# devboard.net
KiCad netlist of a schematic drawn in EAGLE
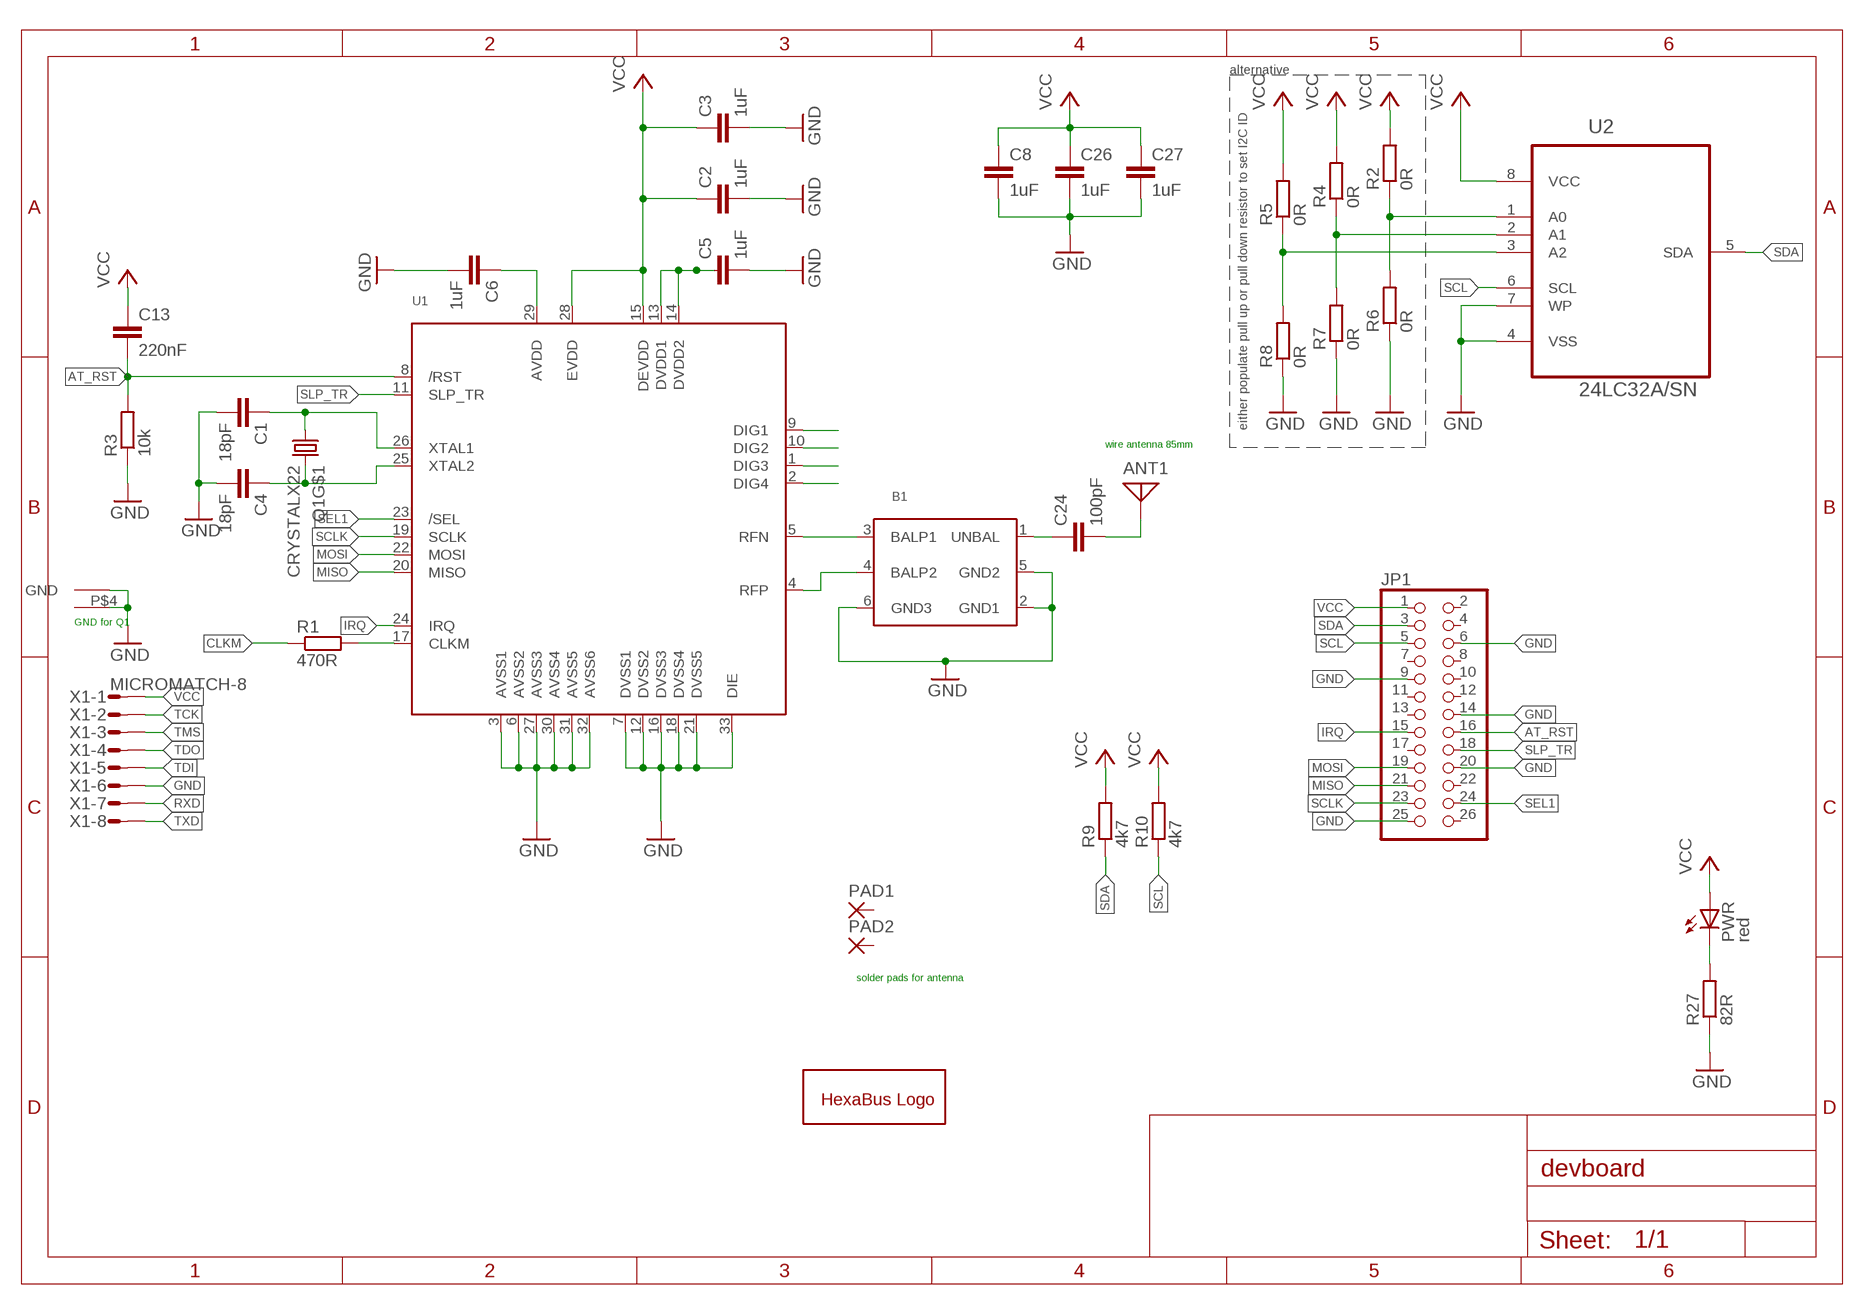
[diagram p0: schematic, sheet 1]

(export (version "E")
  (design (tool "Eeschema 10.0.6"))
  (components
    (comp (ref "ANT1")
      (value "ANTENNA")
      (footprint "eagle-import:PAD-01")
      (libsource (lib "eagle-import") (part "ANTENNA"))
    )
    (comp (ref "B1")
      (value "BALUN+LP")
      (footprint "eagle-import:BALUN0805")
      (libsource (lib "eagle-import") (part "BALUN+LP"))
    )
    (comp (ref "C1")
      (value "18pF")
      (footprint "eagle-import:C0603")
      (libsource (lib "eagle-import") (part "C-EUC0603"))
    )
    (comp (ref "C2")
      (value "1uF")
      (footprint "eagle-import:C0603")
      (libsource (lib "eagle-import") (part "C-EUC0603"))
    )
    (comp (ref "C3")
      (value "1uF")
      (footprint "eagle-import:C0603")
      (libsource (lib "eagle-import") (part "C-EUC0603"))
    )
    (comp (ref "C4")
      (value "18pF")
      (footprint "eagle-import:C0603")
      (libsource (lib "eagle-import") (part "C-EUC0603"))
    )
    (comp (ref "C5")
      (value "1uF")
      (footprint "eagle-import:C0603")
      (libsource (lib "eagle-import") (part "C-EUC0603"))
    )
    (comp (ref "C6")
      (value "1uF")
      (footprint "eagle-import:C0603")
      (libsource (lib "eagle-import") (part "C-EUC0603"))
    )
    (comp (ref "C8")
      (value "1uF")
      (footprint "eagle-import:C0603")
      (libsource (lib "eagle-import") (part "C-EUC0603"))
    )
    (comp (ref "C13")
      (value "220nF")
      (footprint "eagle-import:C0603")
      (libsource (lib "eagle-import") (part "C-EUC0603"))
    )
    (comp (ref "C24")
      (value "100pF")
      (footprint "eagle-import:C0603")
      (libsource (lib "eagle-import") (part "C-EUC0603"))
    )
    (comp (ref "C26")
      (value "1uF")
      (footprint "eagle-import:C0603")
      (libsource (lib "eagle-import") (part "C-EUC0603"))
    )
    (comp (ref "C27")
      (value "1uF")
      (footprint "eagle-import:C0603")
      (libsource (lib "eagle-import") (part "C-EUC0603"))
    )
    (comp (ref "JP1")
      (value "PINHD-2X13")
      (footprint "eagle-import:2X13")
      (libsource (lib "eagle-import") (part "PINHD-2X13"))
    )
    (comp (ref "PAD1")
      (value "SMD2")
      (footprint "eagle-import:SMD1,27-2,54")
      (libsource (lib "eagle-import") (part "SMD2"))
    )
    (comp (ref "PAD2")
      (value "SMD2")
      (footprint "eagle-import:SMD1,27-2,54")
      (libsource (lib "eagle-import") (part "SMD2"))
    )
    (comp (ref "PWR")
      (value "red")
      (footprint "eagle-import:CHIP-LED0603")
      (libsource (lib "eagle-import") (part "LEDCHIP-LED0603"))
    )
    (comp (ref "Q1")
      (value "CRYSTALX22")
      (footprint "eagle-import:X22")
      (libsource (lib "eagle-import") (part "CRYSTALX22"))
    )
    (comp (ref "R1")
      (value "470R")
      (footprint "eagle-import:R0603")
      (libsource (lib "eagle-import") (part "R-EU_R0603"))
    )
    (comp (ref "R2")
      (value "0R")
      (footprint "eagle-import:R0603")
      (libsource (lib "eagle-import") (part "R-EU_R0603"))
    )
    (comp (ref "R3")
      (value "10k")
      (footprint "eagle-import:R0603")
      (libsource (lib "eagle-import") (part "R-EU_R0603"))
    )
    (comp (ref "R4")
      (value "0R")
      (footprint "eagle-import:R0603")
      (libsource (lib "eagle-import") (part "R-EU_R0603"))
    )
    (comp (ref "R5")
      (value "0R")
      (footprint "eagle-import:R0603")
      (libsource (lib "eagle-import") (part "R-EU_R0603"))
    )
    (comp (ref "R6")
      (value "0R")
      (footprint "eagle-import:R0603")
      (libsource (lib "eagle-import") (part "R-EU_R0603"))
    )
    (comp (ref "R7")
      (value "0R")
      (footprint "eagle-import:R0603")
      (libsource (lib "eagle-import") (part "R-EU_R0603"))
    )
    (comp (ref "R8")
      (value "0R")
      (footprint "eagle-import:R0603")
      (libsource (lib "eagle-import") (part "R-EU_R0603"))
    )
    (comp (ref "R9")
      (value "4k7")
      (footprint "eagle-import:R0603")
      (libsource (lib "eagle-import") (part "R-EU_R0603"))
    )
    (comp (ref "R10")
      (value "4k7")
      (footprint "eagle-import:R0603")
      (libsource (lib "eagle-import") (part "R-EU_R0603"))
    )
    (comp (ref "R27")
      (value "82R")
      (footprint "eagle-import:R0603")
      (libsource (lib "eagle-import") (part "R-EU_R0603"))
    )
    (comp (ref "U$1")
      (value "HEXAKRAKE")
      (footprint "eagle-import:HEXAKRAKE")
      (libsource (lib "eagle-import") (part "HEXAKRAKE"))
    )
    (comp (ref "U1")
      (value "AT86RF212")
      (footprint "eagle-import:32QN2")
      (libsource (lib "eagle-import") (part "AT86RF212"))
    )
    (comp (ref "U2")
      (value "24LC32A/SN")
      (footprint "eagle-import:SOIC127P600X175-8N")
      (libsource (lib "eagle-import") (part "24LC32A/SN"))
    )
    (comp (ref "X1")
      (value "MICROMATCH-8")
      (footprint "eagle-import:MICROMATCH-8")
      (fields (field (name "MF") "FARNELL") (field (name "MPN") "7-215464-8"))
      (libsource (lib "eagle-import") (part "MICROMATCH-8"))
    )
  )
  (nets
    (net (code "1") (name "AT_RST") (class "Default")
      (node (ref "C13") (pin "2") (pinfunction "2_2") (pintype "passive"))
      (node (ref "JP1") (pin "16") (pinfunction "16_16") (pintype "passive"))
      (node (ref "R3") (pin "2") (pinfunction "2_2") (pintype "passive"))
      (node (ref "U1") (pin "8") (pinfunction "/RST_8") (pintype "bidirectional"))
    )
    (net (code "2") (name "CLKM") (class "Default")
      (node (ref "R1") (pin "1") (pinfunction "1_1") (pintype "passive"))
    )
    (net (code "3") (name "GND") (class "Default")
      (node (ref "B1") (pin "2") (pinfunction "GND1_2") (pintype "bidirectional"))
      (node (ref "B1") (pin "5") (pinfunction "GND2_5") (pintype "bidirectional"))
      (node (ref "B1") (pin "6") (pinfunction "GND3_6") (pintype "bidirectional"))
      (node (ref "C1") (pin "2") (pinfunction "2_2") (pintype "passive"))
      (node (ref "C2") (pin "2") (pinfunction "2_2") (pintype "passive"))
      (node (ref "C26") (pin "2") (pinfunction "2_2") (pintype "passive"))
      (node (ref "C27") (pin "2") (pinfunction "2_2") (pintype "passive"))
      (node (ref "C3") (pin "2") (pinfunction "2_2") (pintype "passive"))
      (node (ref "C4") (pin "2") (pinfunction "2_2") (pintype "passive"))
      (node (ref "C5") (pin "2") (pinfunction "2_2") (pintype "passive"))
      (node (ref "C6") (pin "2") (pinfunction "2_2") (pintype "passive"))
      (node (ref "C8") (pin "2") (pinfunction "2_2") (pintype "passive"))
      (node (ref "JP1") (pin "14") (pinfunction "14_14") (pintype "passive"))
      (node (ref "JP1") (pin "20") (pinfunction "20_20") (pintype "passive"))
      (node (ref "JP1") (pin "25") (pinfunction "25_25") (pintype "passive"))
      (node (ref "JP1") (pin "6") (pinfunction "6_6") (pintype "passive"))
      (node (ref "JP1") (pin "9") (pinfunction "9_9") (pintype "passive"))
      (node (ref "Q1") (pin "P$2") (pinfunction "GND_P$2") (pintype "bidirectional"))
      (node (ref "Q1") (pin "P$4") (pinfunction "GND1_P$4") (pintype "bidirectional"))
      (node (ref "R27") (pin "1") (pinfunction "1_1") (pintype "passive"))
      (node (ref "R3") (pin "1") (pinfunction "1_1") (pintype "passive"))
      (node (ref "R6") (pin "1") (pinfunction "1_1") (pintype "passive"))
      (node (ref "R7") (pin "1") (pinfunction "1_1") (pintype "passive"))
      (node (ref "R8") (pin "1") (pinfunction "1_1") (pintype "passive"))
      (node (ref "U1") (pin "12") (pinfunction "DVSS2_12") (pintype "bidirectional"))
      (node (ref "U1") (pin "16") (pinfunction "DVSS3_16") (pintype "bidirectional"))
      (node (ref "U1") (pin "18") (pinfunction "DVSS4_18") (pintype "bidirectional"))
      (node (ref "U1") (pin "21") (pinfunction "DVSS5_21") (pintype "bidirectional"))
      (node (ref "U1") (pin "27") (pinfunction "AVSS3_27") (pintype "bidirectional"))
      (node (ref "U1") (pin "3") (pinfunction "AVSS1_3") (pintype "bidirectional"))
      (node (ref "U1") (pin "30") (pinfunction "AVSS4_30") (pintype "bidirectional"))
      (node (ref "U1") (pin "31") (pinfunction "AVSS5_31") (pintype "bidirectional"))
      (node (ref "U1") (pin "32") (pinfunction "AVSS6_32") (pintype "bidirectional"))
      (node (ref "U1") (pin "33") (pinfunction "DIE_33") (pintype "bidirectional"))
      (node (ref "U1") (pin "6") (pinfunction "AVSS2_6") (pintype "bidirectional"))
      (node (ref "U1") (pin "7") (pinfunction "DVSS1_7") (pintype "bidirectional"))
      (node (ref "U2") (pin "4") (pinfunction "VSS_4") (pintype "passive"))
      (node (ref "U2") (pin "7") (pinfunction "WP_7") (pintype "input"))
      (node (ref "X1") (pin "6") (pinfunction "S_6") (pintype "passive"))
    )
    (net (code "4") (name "IRQ") (class "Default")
      (node (ref "JP1") (pin "15") (pinfunction "15_15") (pintype "passive"))
      (node (ref "U1") (pin "24") (pinfunction "IRQ_24") (pintype "bidirectional"))
    )
    (net (code "5") (name "MISO") (class "Default")
      (node (ref "JP1") (pin "21") (pinfunction "21_21") (pintype "passive"))
      (node (ref "U1") (pin "20") (pinfunction "MISO_20") (pintype "bidirectional"))
    )
    (net (code "6") (name "MOSI") (class "Default")
      (node (ref "JP1") (pin "19") (pinfunction "19_19") (pintype "passive"))
      (node (ref "U1") (pin "22") (pinfunction "MOSI_22") (pintype "bidirectional"))
    )
    (net (code "7") (name "Net-(ANT1-Pad1)") (class "Default")
      (node (ref "ANT1") (pin "1") (pinfunction "1_1") (pintype "output"))
      (node (ref "C24") (pin "2") (pinfunction "2_2") (pintype "passive"))
    )
    (net (code "8") (name "Net-(B1-BALP1)") (class "Default")
      (node (ref "B1") (pin "3") (pinfunction "BALP1_3") (pintype "bidirectional"))
      (node (ref "U1") (pin "5") (pinfunction "RFN_5") (pintype "bidirectional"))
    )
    (net (code "9") (name "Net-(B1-BALP2)") (class "Default")
      (node (ref "B1") (pin "4") (pinfunction "BALP2_4") (pintype "bidirectional"))
      (node (ref "U1") (pin "4") (pinfunction "RFP_4") (pintype "bidirectional"))
    )
    (net (code "10") (name "Net-(B1-UNBAL)") (class "Default")
      (node (ref "B1") (pin "1") (pinfunction "UNBAL_1") (pintype "bidirectional"))
      (node (ref "C24") (pin "1") (pinfunction "1_1") (pintype "passive"))
    )
    (net (code "11") (name "Net-(PWR-PadC)") (class "Default")
      (node (ref "PWR") (pin "C") (pinfunction "C_C") (pintype "passive"))
      (node (ref "R27") (pin "2") (pinfunction "2_2") (pintype "passive"))
    )
    (net (code "12") (name "Net-(Q1A-1)") (class "Default")
      (node (ref "C1") (pin "1") (pinfunction "1_1") (pintype "passive"))
      (node (ref "Q1") (pin "P$1") (pinfunction "1_P$1") (pintype "passive"))
      (node (ref "U1") (pin "26") (pinfunction "XTAL1_26") (pintype "bidirectional"))
    )
    (net (code "13") (name "Net-(Q1A-2)") (class "Default")
      (node (ref "C4") (pin "1") (pinfunction "1_1") (pintype "passive"))
      (node (ref "Q1") (pin "P$3") (pinfunction "2_P$3") (pintype "passive"))
      (node (ref "U1") (pin "25") (pinfunction "XTAL2_25") (pintype "bidirectional"))
    )
    (net (code "14") (name "Net-(U1-AVDD)") (class "Default")
      (node (ref "C6") (pin "1") (pinfunction "1_1") (pintype "passive"))
      (node (ref "U1") (pin "29") (pinfunction "AVDD_29") (pintype "bidirectional"))
    )
    (net (code "15") (name "Net-(U1-CLKM)") (class "Default")
      (node (ref "R1") (pin "2") (pinfunction "2_2") (pintype "passive"))
      (node (ref "U1") (pin "17") (pinfunction "CLKM_17") (pintype "bidirectional"))
    )
    (net (code "16") (name "Net-(U1-DVDD1)") (class "Default")
      (node (ref "C5") (pin "1") (pinfunction "1_1") (pintype "passive"))
      (node (ref "U1") (pin "13") (pinfunction "DVDD1_13") (pintype "bidirectional"))
      (node (ref "U1") (pin "14") (pinfunction "DVDD2_14") (pintype "bidirectional"))
    )
    (net (code "17") (name "Net-(U2-A0)") (class "Default")
      (node (ref "R2") (pin "1") (pinfunction "1_1") (pintype "passive"))
      (node (ref "R6") (pin "2") (pinfunction "2_2") (pintype "passive"))
      (node (ref "U2") (pin "1") (pinfunction "A0_1") (pintype "input"))
    )
    (net (code "18") (name "Net-(U2-A1)") (class "Default")
      (node (ref "R4") (pin "1") (pinfunction "1_1") (pintype "passive"))
      (node (ref "R7") (pin "2") (pinfunction "2_2") (pintype "passive"))
      (node (ref "U2") (pin "2") (pinfunction "A1_2") (pintype "input"))
    )
    (net (code "19") (name "Net-(U2-A2)") (class "Default")
      (node (ref "R5") (pin "1") (pinfunction "1_1") (pintype "passive"))
      (node (ref "R8") (pin "2") (pinfunction "2_2") (pintype "passive"))
      (node (ref "U2") (pin "3") (pinfunction "A2_3") (pintype "input"))
    )
    (net (code "20") (name "RXD") (class "Default")
      (node (ref "X1") (pin "7") (pinfunction "S_7") (pintype "passive"))
    )
    (net (code "21") (name "SCL") (class "Default")
      (node (ref "JP1") (pin "5") (pinfunction "5_5") (pintype "passive"))
      (node (ref "R10") (pin "1") (pinfunction "1_1") (pintype "passive"))
      (node (ref "U2") (pin "6") (pinfunction "SCL_6") (pintype "input"))
    )
    (net (code "22") (name "SCLK") (class "Default")
      (node (ref "JP1") (pin "23") (pinfunction "23_23") (pintype "passive"))
      (node (ref "U1") (pin "19") (pinfunction "SCLK_19") (pintype "bidirectional"))
    )
    (net (code "23") (name "SDA") (class "Default")
      (node (ref "JP1") (pin "3") (pinfunction "3_3") (pintype "passive"))
      (node (ref "R9") (pin "1") (pinfunction "1_1") (pintype "passive"))
      (node (ref "U2") (pin "5") (pinfunction "SDA_5") (pintype "bidirectional"))
    )
    (net (code "24") (name "SEL1") (class "Default")
      (node (ref "JP1") (pin "24") (pinfunction "24_24") (pintype "passive"))
      (node (ref "U1") (pin "23") (pinfunction "/SEL_23") (pintype "bidirectional"))
    )
    (net (code "25") (name "SLP_TR") (class "Default")
      (node (ref "JP1") (pin "18") (pinfunction "18_18") (pintype "passive"))
      (node (ref "U1") (pin "11") (pinfunction "SLP_TR_11") (pintype "bidirectional"))
    )
    (net (code "26") (name "TCK") (class "Default")
      (node (ref "X1") (pin "2") (pinfunction "S_2") (pintype "passive"))
    )
    (net (code "27") (name "TDI") (class "Default")
      (node (ref "X1") (pin "5") (pinfunction "S_5") (pintype "passive"))
    )
    (net (code "28") (name "TDO") (class "Default")
      (node (ref "X1") (pin "4") (pinfunction "S_4") (pintype "passive"))
    )
    (net (code "29") (name "TMS") (class "Default")
      (node (ref "X1") (pin "3") (pinfunction "S_3") (pintype "passive"))
    )
    (net (code "30") (name "TXD") (class "Default")
      (node (ref "X1") (pin "8") (pinfunction "S_8") (pintype "passive"))
    )
    (net (code "31") (name "VCC") (class "Default")
      (node (ref "C13") (pin "1") (pinfunction "1_1") (pintype "passive"))
      (node (ref "C2") (pin "1") (pinfunction "1_1") (pintype "passive"))
      (node (ref "C26") (pin "1") (pinfunction "1_1") (pintype "passive"))
      (node (ref "C27") (pin "1") (pinfunction "1_1") (pintype "passive"))
      (node (ref "C3") (pin "1") (pinfunction "1_1") (pintype "passive"))
      (node (ref "C8") (pin "1") (pinfunction "1_1") (pintype "passive"))
      (node (ref "JP1") (pin "1") (pinfunction "1_1") (pintype "passive"))
      (node (ref "PWR") (pin "A") (pinfunction "A_A") (pintype "passive"))
      (node (ref "R10") (pin "2") (pinfunction "2_2") (pintype "passive"))
      (node (ref "R2") (pin "2") (pinfunction "2_2") (pintype "passive"))
      (node (ref "R4") (pin "2") (pinfunction "2_2") (pintype "passive"))
      (node (ref "R5") (pin "2") (pinfunction "2_2") (pintype "passive"))
      (node (ref "R9") (pin "2") (pinfunction "2_2") (pintype "passive"))
      (node (ref "U1") (pin "15") (pinfunction "DEVDD_15") (pintype "bidirectional"))
      (node (ref "U1") (pin "28") (pinfunction "EVDD_28") (pintype "bidirectional"))
      (node (ref "U2") (pin "8") (pinfunction "VCC_8") (pintype "power_in"))
      (node (ref "X1") (pin "1") (pinfunction "S_1") (pintype "passive"))
    )
    (net (code "32") (name "unconnected-(JP1-Pad2)") (class "Default")
      (node (ref "JP1") (pin "2") (pinfunction "2_2") (pintype "passive"))
    )
    (net (code "33") (name "unconnected-(JP1-Pad4)") (class "Default")
      (node (ref "JP1") (pin "4") (pinfunction "4_4") (pintype "passive"))
    )
    (net (code "34") (name "unconnected-(JP1-Pad7)") (class "Default")
      (node (ref "JP1") (pin "7") (pinfunction "7_7") (pintype "passive"))
    )
    (net (code "35") (name "unconnected-(JP1-Pad8)") (class "Default")
      (node (ref "JP1") (pin "8") (pinfunction "8_8") (pintype "passive"))
    )
    (net (code "36") (name "unconnected-(JP1-Pad10)") (class "Default")
      (node (ref "JP1") (pin "10") (pinfunction "10_10") (pintype "passive"))
    )
    (net (code "37") (name "unconnected-(JP1-Pad11)") (class "Default")
      (node (ref "JP1") (pin "11") (pinfunction "11_11") (pintype "passive"))
    )
    (net (code "38") (name "unconnected-(JP1-Pad12)") (class "Default")
      (node (ref "JP1") (pin "12") (pinfunction "12_12") (pintype "passive"))
    )
    (net (code "39") (name "unconnected-(JP1-Pad13)") (class "Default")
      (node (ref "JP1") (pin "13") (pinfunction "13_13") (pintype "passive"))
    )
    (net (code "40") (name "unconnected-(JP1-Pad17)") (class "Default")
      (node (ref "JP1") (pin "17") (pinfunction "17_17") (pintype "passive"))
    )
    (net (code "41") (name "unconnected-(JP1-Pad22)") (class "Default")
      (node (ref "JP1") (pin "22") (pinfunction "22_22") (pintype "passive"))
    )
    (net (code "42") (name "unconnected-(JP1-Pad26)") (class "Default")
      (node (ref "JP1") (pin "26") (pinfunction "26_26") (pintype "passive"))
    )
    (net (code "43") (name "unconnected-(PAD1-P-Pad1)") (class "Default")
      (node (ref "PAD1") (pin "1") (pinfunction "P_1") (pintype "passive"))
    )
    (net (code "44") (name "unconnected-(PAD2-P-Pad1)") (class "Default")
      (node (ref "PAD2") (pin "1") (pinfunction "P_1") (pintype "passive"))
    )
    (net (code "45") (name "unconnected-(U1-DIG1-Pad9)") (class "Default")
      (node (ref "U1") (pin "9") (pinfunction "DIG1_9") (pintype "bidirectional"))
    )
    (net (code "46") (name "unconnected-(U1-DIG2-Pad10)") (class "Default")
      (node (ref "U1") (pin "10") (pinfunction "DIG2_10") (pintype "bidirectional"))
    )
    (net (code "47") (name "unconnected-(U1-DIG3-Pad1)") (class "Default")
      (node (ref "U1") (pin "1") (pinfunction "DIG3_1") (pintype "bidirectional"))
    )
    (net (code "48") (name "unconnected-(U1-DIG4-Pad2)") (class "Default")
      (node (ref "U1") (pin "2") (pinfunction "DIG4_2") (pintype "bidirectional"))
    )
  )
)
